# ECE4180_DP_Main.net
KiCad netlist of a schematic drawn in EAGLE
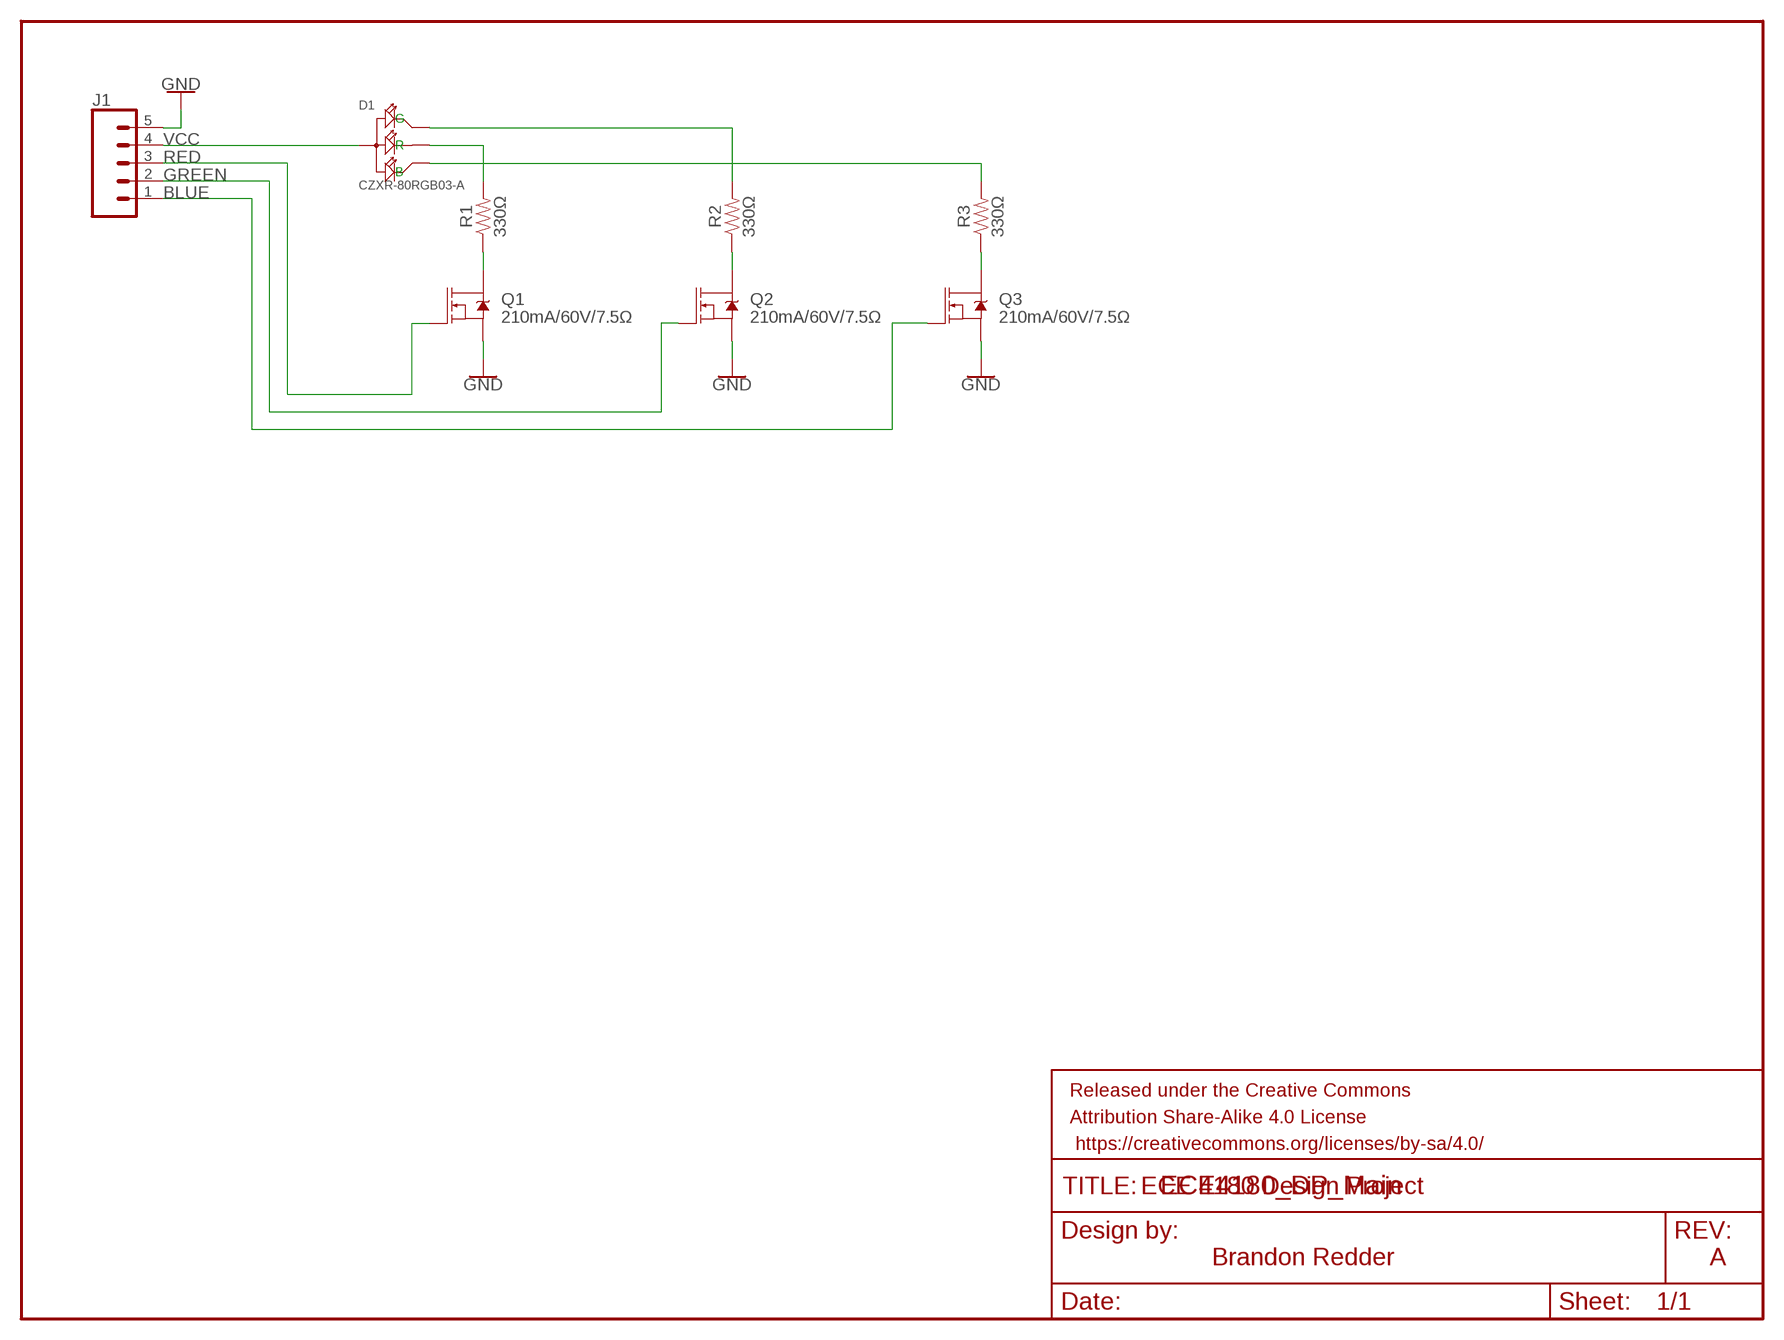
[diagram p0: schematic, sheet 1]

(export (version "E")
  (design (tool "Eeschema 10.0.6"))
  (components
    (comp (ref "D1")
      (value "CZXR-80RGB03-A")
      (footprint "eagle-import:LED4-2.0-D8.0MM")
      (libsource (lib "eagle-import") (part "DIP-LED-RGB-COMMON-ANODE(4P-D8MM)"))
    )
    (comp (ref "FRAME")
      (value "FRAME-LETTERNO_PACKAGE")
      (footprint "eagle-import:DUMMY")
      (fields (field (name "DESIGNER") "Brandon Redder"))
      (libsource (lib "eagle-import") (part "FRAME-LETTERNO_PACKAGE"))
    )
    (comp (ref "J1")
      (value "CONN_05LOCK")
      (footprint "eagle-import:1X05_LOCK")
      (libsource (lib "eagle-import") (part "CONN_05LOCK"))
    )
    (comp (ref "Q1")
      (value "210mA/60V/7.5Ω")
      (footprint "eagle-import:SOT23-3")
      (libsource (lib "eagle-import") (part "MOSFET-NCH-AO3404A"))
    )
    (comp (ref "Q2")
      (value "210mA/60V/7.5Ω")
      (footprint "eagle-import:SOT23-3")
      (libsource (lib "eagle-import") (part "MOSFET-NCH-AO3404A"))
    )
    (comp (ref "Q3")
      (value "210mA/60V/7.5Ω")
      (footprint "eagle-import:SOT23-3")
      (libsource (lib "eagle-import") (part "MOSFET-NCH-AO3404A"))
    )
    (comp (ref "R1")
      (value "330Ω")
      (footprint "eagle-import:0805")
      (libsource (lib "eagle-import") (part "RESISTOR0805"))
    )
    (comp (ref "R2")
      (value "330Ω")
      (footprint "eagle-import:0805")
      (libsource (lib "eagle-import") (part "RESISTOR0805"))
    )
    (comp (ref "R3")
      (value "330Ω")
      (footprint "eagle-import:0805")
      (libsource (lib "eagle-import") (part "RESISTOR0805"))
    )
  )
  (nets
    (net (code "1") (name "/BLUE") (class "Default")
      (node (ref "J1") (pin "1") (pinfunction "1_1") (pintype "passive"))
      (node (ref "Q3") (pin "1") (pinfunction "G_1") (pintype "bidirectional"))
    )
    (net (code "2") (name "/GREEN") (class "Default")
      (node (ref "J1") (pin "2") (pinfunction "2_2") (pintype "passive"))
      (node (ref "Q2") (pin "1") (pinfunction "G_1") (pintype "bidirectional"))
    )
    (net (code "3") (name "/RED") (class "Default")
      (node (ref "J1") (pin "3") (pinfunction "3_3") (pintype "passive"))
      (node (ref "Q1") (pin "1") (pinfunction "G_1") (pintype "bidirectional"))
    )
    (net (code "4") (name "/VCC") (class "Default")
      (node (ref "D1") (pin "2") (pinfunction "+_2") (pintype "bidirectional"))
      (node (ref "J1") (pin "4") (pinfunction "4_4") (pintype "passive"))
    )
    (net (code "5") (name "GND") (class "Default")
      (node (ref "J1") (pin "5") (pinfunction "5_5") (pintype "passive"))
      (node (ref "Q1") (pin "2") (pinfunction "S_2") (pintype "bidirectional"))
      (node (ref "Q2") (pin "2") (pinfunction "S_2") (pintype "bidirectional"))
      (node (ref "Q3") (pin "2") (pinfunction "S_2") (pintype "bidirectional"))
    )
    (net (code "6") (name "Net-(D1-B)") (class "Default")
      (node (ref "D1") (pin "4") (pinfunction "B_4") (pintype "bidirectional"))
      (node (ref "R3") (pin "2") (pinfunction "2_2") (pintype "passive"))
    )
    (net (code "7") (name "Net-(D1-G)") (class "Default")
      (node (ref "D1") (pin "3") (pinfunction "G_3") (pintype "bidirectional"))
      (node (ref "R2") (pin "2") (pinfunction "2_2") (pintype "passive"))
    )
    (net (code "8") (name "Net-(D1-R)") (class "Default")
      (node (ref "D1") (pin "1") (pinfunction "R_1") (pintype "bidirectional"))
      (node (ref "R1") (pin "2") (pinfunction "2_2") (pintype "passive"))
    )
    (net (code "9") (name "Net-(Q1-D)") (class "Default")
      (node (ref "Q1") (pin "3") (pinfunction "D_3") (pintype "bidirectional"))
      (node (ref "R1") (pin "1") (pinfunction "1_1") (pintype "passive"))
    )
    (net (code "10") (name "Net-(Q2-D)") (class "Default")
      (node (ref "Q2") (pin "3") (pinfunction "D_3") (pintype "bidirectional"))
      (node (ref "R2") (pin "1") (pinfunction "1_1") (pintype "passive"))
    )
    (net (code "11") (name "Net-(Q3-D)") (class "Default")
      (node (ref "Q3") (pin "3") (pinfunction "D_3") (pintype "bidirectional"))
      (node (ref "R3") (pin "1") (pinfunction "1_1") (pintype "passive"))
    )
  )
)
